# IR_Diode_PCB.net
KiCad netlist of a schematic drawn in Altium Designer
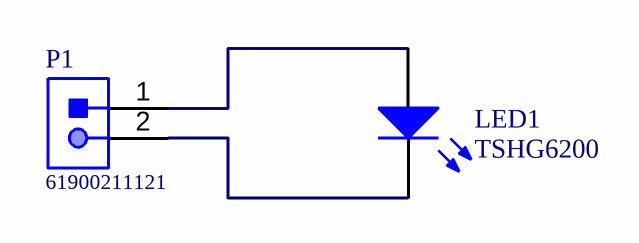
[diagram p0: IR_Diode_PCB.SchDoc]

(export (version "E")
  (design (tool "Eeschema 10.0.6"))
  (components
    (comp (ref "LED1")
      (value "TSHG6200")
      (footprint "Type 5mm")
      (fields (field (name "PARTNUMBER") "151053GS03000") (field (name "MANUFACTURER") "Wuerth Elektronik"))
      (libsource (lib "Altium Content Vault") (part "WE-LED_K1A2-2"))
    )
    (comp (ref "P1")
      (value "61900211121")
      (footprint "61900211121")
      (description "Male Locking Header WR-WTB, THT, Vertical, pitch 2.54 mm, 1 x 2 position")
      (fields (field (name "MANUFACTURER") "Wurth Elektronik") (field (name "PUBLISHER") "WurthElektronik"))
      (libsource (lib "Altium Content Vault") (part "WE-CN-1P-M-R2"))
    )
  )
  (nets
    (net (code "1") (name "Net-(LED1-A)") (class "Default")
      (node (ref "LED1") (pin "2") (pinfunction "A_2") (pintype "passive"))
      (node (ref "P1") (pin "1") (pinfunction "1_1") (pintype "passive"))
    )
    (net (code "2") (name "Net-(LED1-K)") (class "Default")
      (node (ref "LED1") (pin "1") (pinfunction "K_1") (pintype "passive"))
      (node (ref "P1") (pin "2") (pinfunction "2_2") (pintype "passive"))
    )
  )
)
